# ZabavyBulb.net
KiCad netlist of a schematic drawn in EAGLE
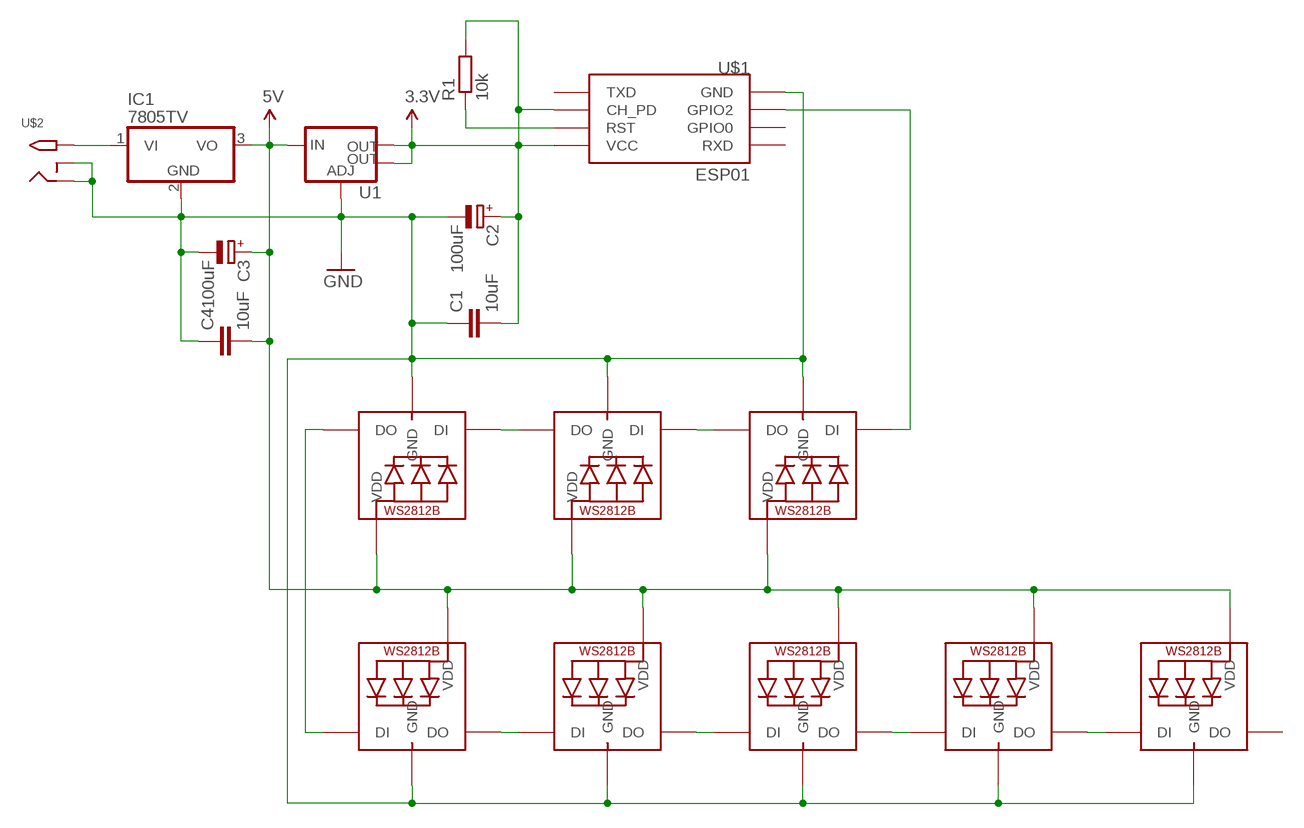
[diagram p0: schematic, sheet 1]

(export (version "E")
  (design (tool "Eeschema 10.0.6"))
  (components
    (comp (ref "C1")
      (value "10uF")
      (footprint "eagle-import:C050-024X044")
      (libsource (lib "eagle-import") (part "C-EU050-024X044"))
    )
    (comp (ref "C2")
      (value "100uF")
      (footprint "eagle-import:E2,5-6")
      (libsource (lib "eagle-import") (part "CPOL-EUE2.5-6"))
    )
    (comp (ref "C3")
      (value "100uF")
      (footprint "eagle-import:E2,5-6")
      (libsource (lib "eagle-import") (part "CPOL-EUE2.5-6"))
    )
    (comp (ref "C4")
      (value "10uF")
      (footprint "eagle-import:C050-024X044")
      (libsource (lib "eagle-import") (part "C-EU050-024X044"))
    )
    (comp (ref "IC1")
      (value "7805TV")
      (footprint "eagle-import:TO220V")
      (libsource (lib "eagle-import") (part "78TV05"))
    )
    (comp (ref "LED1")
      (value "WS2812B3535")
      (footprint "eagle-import:LED3535")
      (libsource (lib "eagle-import") (part "WS2812B3535"))
    )
    (comp (ref "LED2")
      (value "WS2812B3535")
      (footprint "eagle-import:LED3535")
      (libsource (lib "eagle-import") (part "WS2812B3535"))
    )
    (comp (ref "LED3")
      (value "WS2812B3535")
      (footprint "eagle-import:LED3535")
      (libsource (lib "eagle-import") (part "WS2812B3535"))
    )
    (comp (ref "LED4")
      (value "WS2812B3535")
      (footprint "eagle-import:LED3535")
      (libsource (lib "eagle-import") (part "WS2812B3535"))
    )
    (comp (ref "LED5")
      (value "WS2812B3535")
      (footprint "eagle-import:LED3535")
      (libsource (lib "eagle-import") (part "WS2812B3535"))
    )
    (comp (ref "LED6")
      (value "WS2812B3535")
      (footprint "eagle-import:LED3535")
      (libsource (lib "eagle-import") (part "WS2812B3535"))
    )
    (comp (ref "LED7")
      (value "WS2812B3535")
      (footprint "eagle-import:LED3535")
      (libsource (lib "eagle-import") (part "WS2812B3535"))
    )
    (comp (ref "LED8")
      (value "WS2812B3535")
      (footprint "eagle-import:LED3535")
      (libsource (lib "eagle-import") (part "WS2812B3535"))
    )
    (comp (ref "R1")
      (value "10k")
      (footprint "eagle-import:0207_10")
      (libsource (lib "eagle-import") (part "R-EU_0207/10"))
    )
    (comp (ref "U$1")
      (value "ESP01")
      (footprint "eagle-import:ESP01")
      (libsource (lib "eagle-import") (part "ESP01"))
    )
    (comp (ref "U$2")
      (value "2.1MMJACKTHM")
      (footprint "eagle-import:PJ-102A")
      (libsource (lib "eagle-import") (part "2.1MMJACKTHM"))
    )
    (comp (ref "U1")
      (value "V_REG_LM1117SOT223")
      (footprint "eagle-import:SOT223")
      (libsource (lib "eagle-import") (part "V_REG_LM1117SOT223"))
    )
  )
  (nets
    (net (code "1") (name "3.3V") (class "Default")
      (node (ref "C1") (pin "2") (pinfunction "2_2") (pintype "passive"))
      (node (ref "C2") (pin "+") (pinfunction "+_+") (pintype "passive"))
      (node (ref "R1") (pin "2") (pinfunction "2_2") (pintype "passive"))
      (node (ref "U$1") (pin "CH_PD") (pinfunction "CH_PD_CH_PD") (pintype "bidirectional"))
      (node (ref "U$1") (pin "VCC") (pinfunction "VCC_VCC") (pintype "bidirectional"))
      (node (ref "U1") (pin "2") (pinfunction "OUT_2") (pintype "output"))
      (node (ref "U1") (pin "4") (pinfunction "OUT_4") (pintype "output"))
    )
    (net (code "2") (name "5V") (class "Default")
      (node (ref "C3") (pin "+") (pinfunction "+_+") (pintype "passive"))
      (node (ref "C4") (pin "2") (pinfunction "2_2") (pintype "passive"))
      (node (ref "IC1") (pin "3") (pinfunction "VO_3") (pintype "passive"))
      (node (ref "LED1") (pin "2") (pinfunction "VDD_2") (pintype "power_in"))
      (node (ref "LED2") (pin "2") (pinfunction "VDD_2") (pintype "power_in"))
      (node (ref "LED3") (pin "2") (pinfunction "VDD_2") (pintype "power_in"))
      (node (ref "LED4") (pin "2") (pinfunction "VDD_2") (pintype "power_in"))
      (node (ref "LED5") (pin "2") (pinfunction "VDD_2") (pintype "power_in"))
      (node (ref "LED6") (pin "2") (pinfunction "VDD_2") (pintype "power_in"))
      (node (ref "LED7") (pin "2") (pinfunction "VDD_2") (pintype "power_in"))
      (node (ref "LED8") (pin "2") (pinfunction "VDD_2") (pintype "power_in"))
      (node (ref "U1") (pin "3") (pinfunction "IN_3") (pintype "input"))
    )
    (net (code "3") (name "GND") (class "Default")
      (node (ref "C1") (pin "1") (pinfunction "1_1") (pintype "passive"))
      (node (ref "C2") (pin "-") (pinfunction "-_-") (pintype "passive"))
      (node (ref "C3") (pin "-") (pinfunction "-_-") (pintype "passive"))
      (node (ref "C4") (pin "1") (pinfunction "1_1") (pintype "passive"))
      (node (ref "IC1") (pin "2") (pinfunction "GND_2") (pintype "passive"))
      (node (ref "LED1") (pin "4") (pinfunction "GND_4") (pintype "power_in"))
      (node (ref "LED2") (pin "4") (pinfunction "GND_4") (pintype "power_in"))
      (node (ref "LED3") (pin "4") (pinfunction "GND_4") (pintype "power_in"))
      (node (ref "LED4") (pin "4") (pinfunction "GND_4") (pintype "power_in"))
      (node (ref "LED5") (pin "4") (pinfunction "GND_4") (pintype "power_in"))
      (node (ref "LED6") (pin "4") (pinfunction "GND_4") (pintype "power_in"))
      (node (ref "LED7") (pin "4") (pinfunction "GND_4") (pintype "power_in"))
      (node (ref "LED8") (pin "4") (pinfunction "GND_4") (pintype "power_in"))
      (node (ref "U$1") (pin "GND") (pinfunction "GND_GND") (pintype "bidirectional"))
      (node (ref "U$2") (pin "RING") (pinfunction "RING_RING") (pintype "bidirectional"))
      (node (ref "U$2") (pin "RING_SW") (pinfunction "RING_SW_RING_SW") (pintype "bidirectional"))
      (node (ref "U1") (pin "1") (pinfunction "ADJ_1") (pintype "input"))
    )
    (net (code "4") (name "Net-(IC1-VI)") (class "Default")
      (node (ref "IC1") (pin "1") (pinfunction "VI_1") (pintype "input"))
      (node (ref "U$2") (pin "TIP") (pinfunction "TIP_TIP") (pintype "bidirectional"))
    )
    (net (code "5") (name "Net-(LED1-DI)") (class "Default")
      (node (ref "LED1") (pin "1") (pinfunction "DI_1") (pintype "input"))
      (node (ref "U$1") (pin "GPIO2") (pinfunction "GPIO2_GPIO2") (pintype "bidirectional"))
    )
    (net (code "6") (name "Net-(LED1-DO)") (class "Default")
      (node (ref "LED1") (pin "3") (pinfunction "DO_3") (pintype "output"))
      (node (ref "LED2") (pin "1") (pinfunction "DI_1") (pintype "input"))
    )
    (net (code "7") (name "Net-(LED2-DO)") (class "Default")
      (node (ref "LED2") (pin "3") (pinfunction "DO_3") (pintype "output"))
      (node (ref "LED3") (pin "1") (pinfunction "DI_1") (pintype "input"))
    )
    (net (code "8") (name "Net-(LED3-DO)") (class "Default")
      (node (ref "LED3") (pin "3") (pinfunction "DO_3") (pintype "output"))
      (node (ref "LED4") (pin "1") (pinfunction "DI_1") (pintype "input"))
    )
    (net (code "9") (name "Net-(LED4-DO)") (class "Default")
      (node (ref "LED4") (pin "3") (pinfunction "DO_3") (pintype "output"))
      (node (ref "LED5") (pin "1") (pinfunction "DI_1") (pintype "input"))
    )
    (net (code "10") (name "Net-(LED5-DO)") (class "Default")
      (node (ref "LED5") (pin "3") (pinfunction "DO_3") (pintype "output"))
      (node (ref "LED6") (pin "1") (pinfunction "DI_1") (pintype "input"))
    )
    (net (code "11") (name "Net-(LED6-DO)") (class "Default")
      (node (ref "LED6") (pin "3") (pinfunction "DO_3") (pintype "output"))
      (node (ref "LED7") (pin "1") (pinfunction "DI_1") (pintype "input"))
    )
    (net (code "12") (name "Net-(LED7-DO)") (class "Default")
      (node (ref "LED7") (pin "3") (pinfunction "DO_3") (pintype "output"))
      (node (ref "LED8") (pin "1") (pinfunction "DI_1") (pintype "input"))
    )
    (net (code "13") (name "Net-(R1-Pad1)") (class "Default")
      (node (ref "R1") (pin "1") (pinfunction "1_1") (pintype "passive"))
      (node (ref "U$1") (pin "RST") (pinfunction "RST_RST") (pintype "bidirectional"))
    )
    (net (code "14") (name "unconnected-(LED8-DO-Pad3)") (class "Default")
      (node (ref "LED8") (pin "3") (pinfunction "DO_3") (pintype "output"))
    )
    (net (code "15") (name "unconnected-(U$1-PadGPIO0)") (class "Default")
      (node (ref "U$1") (pin "GPIO0") (pinfunction "GPIO0_GPIO0") (pintype "bidirectional"))
    )
    (net (code "16") (name "unconnected-(U$1-RXD-PadRX)") (class "Default")
      (node (ref "U$1") (pin "RX") (pinfunction "RXD_RX") (pintype "bidirectional"))
    )
    (net (code "17") (name "unconnected-(U$1-TXD-PadTX)") (class "Default")
      (node (ref "U$1") (pin "TX") (pinfunction "TXD_TX") (pintype "bidirectional"))
    )
  )
)
